# Sheet1.net
KiCad netlist of a schematic drawn in Altium Designer
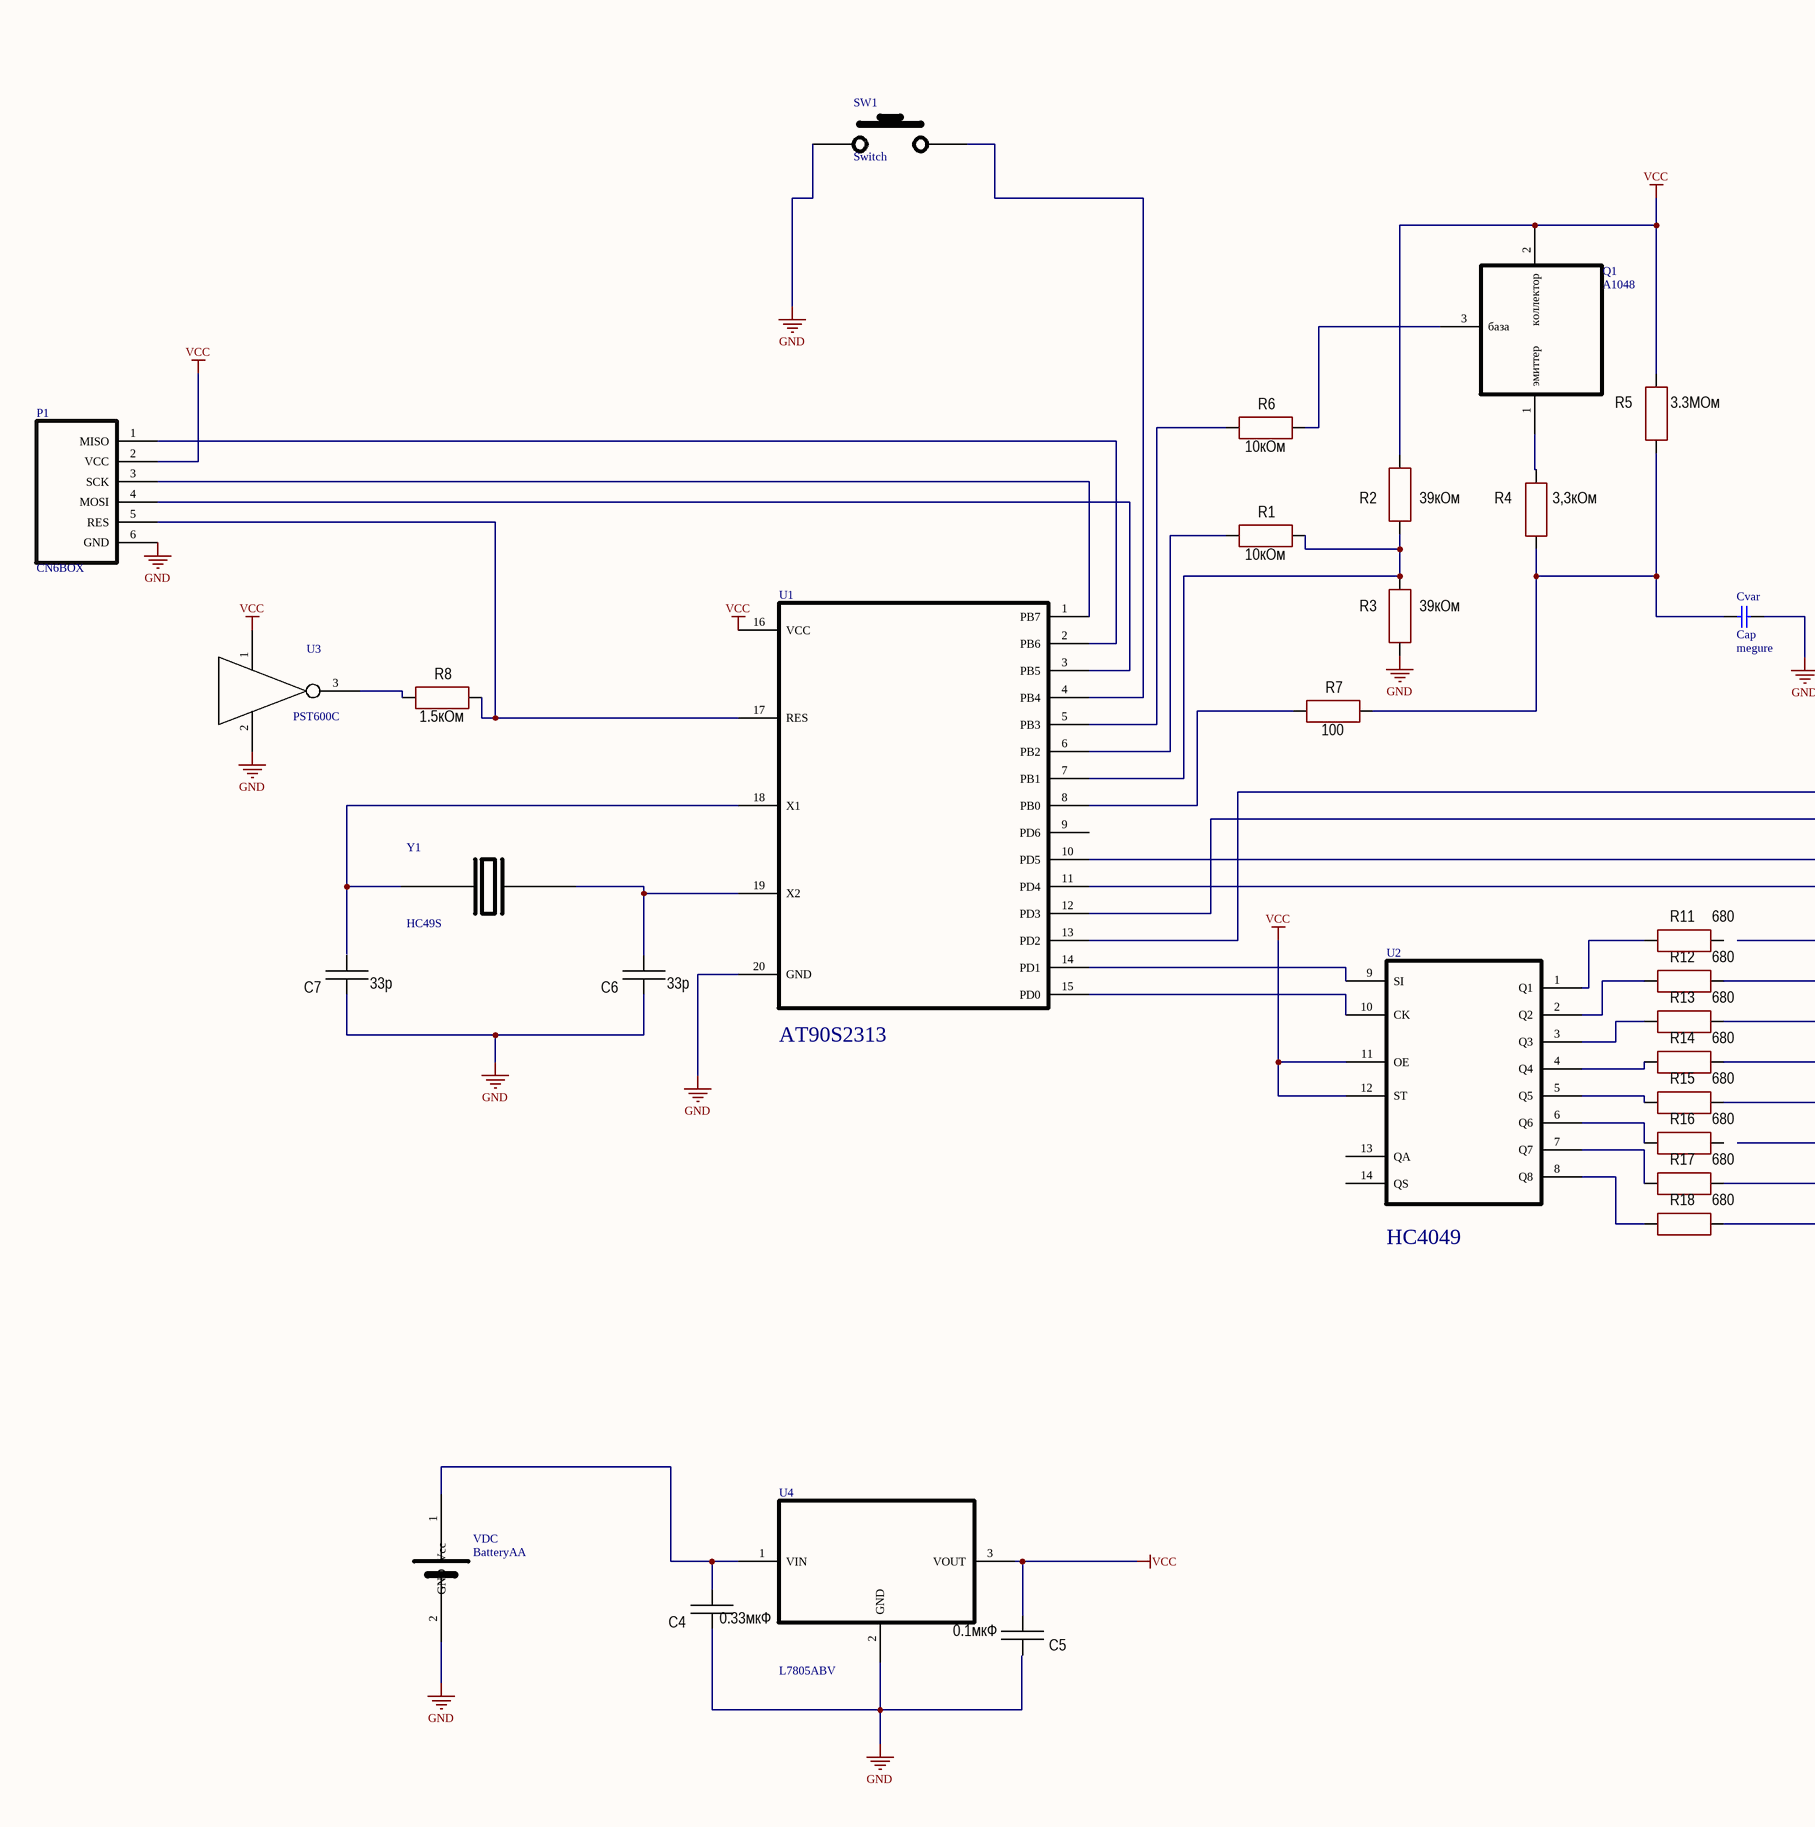
[diagram p0: Sheet1.SchDoc, left]
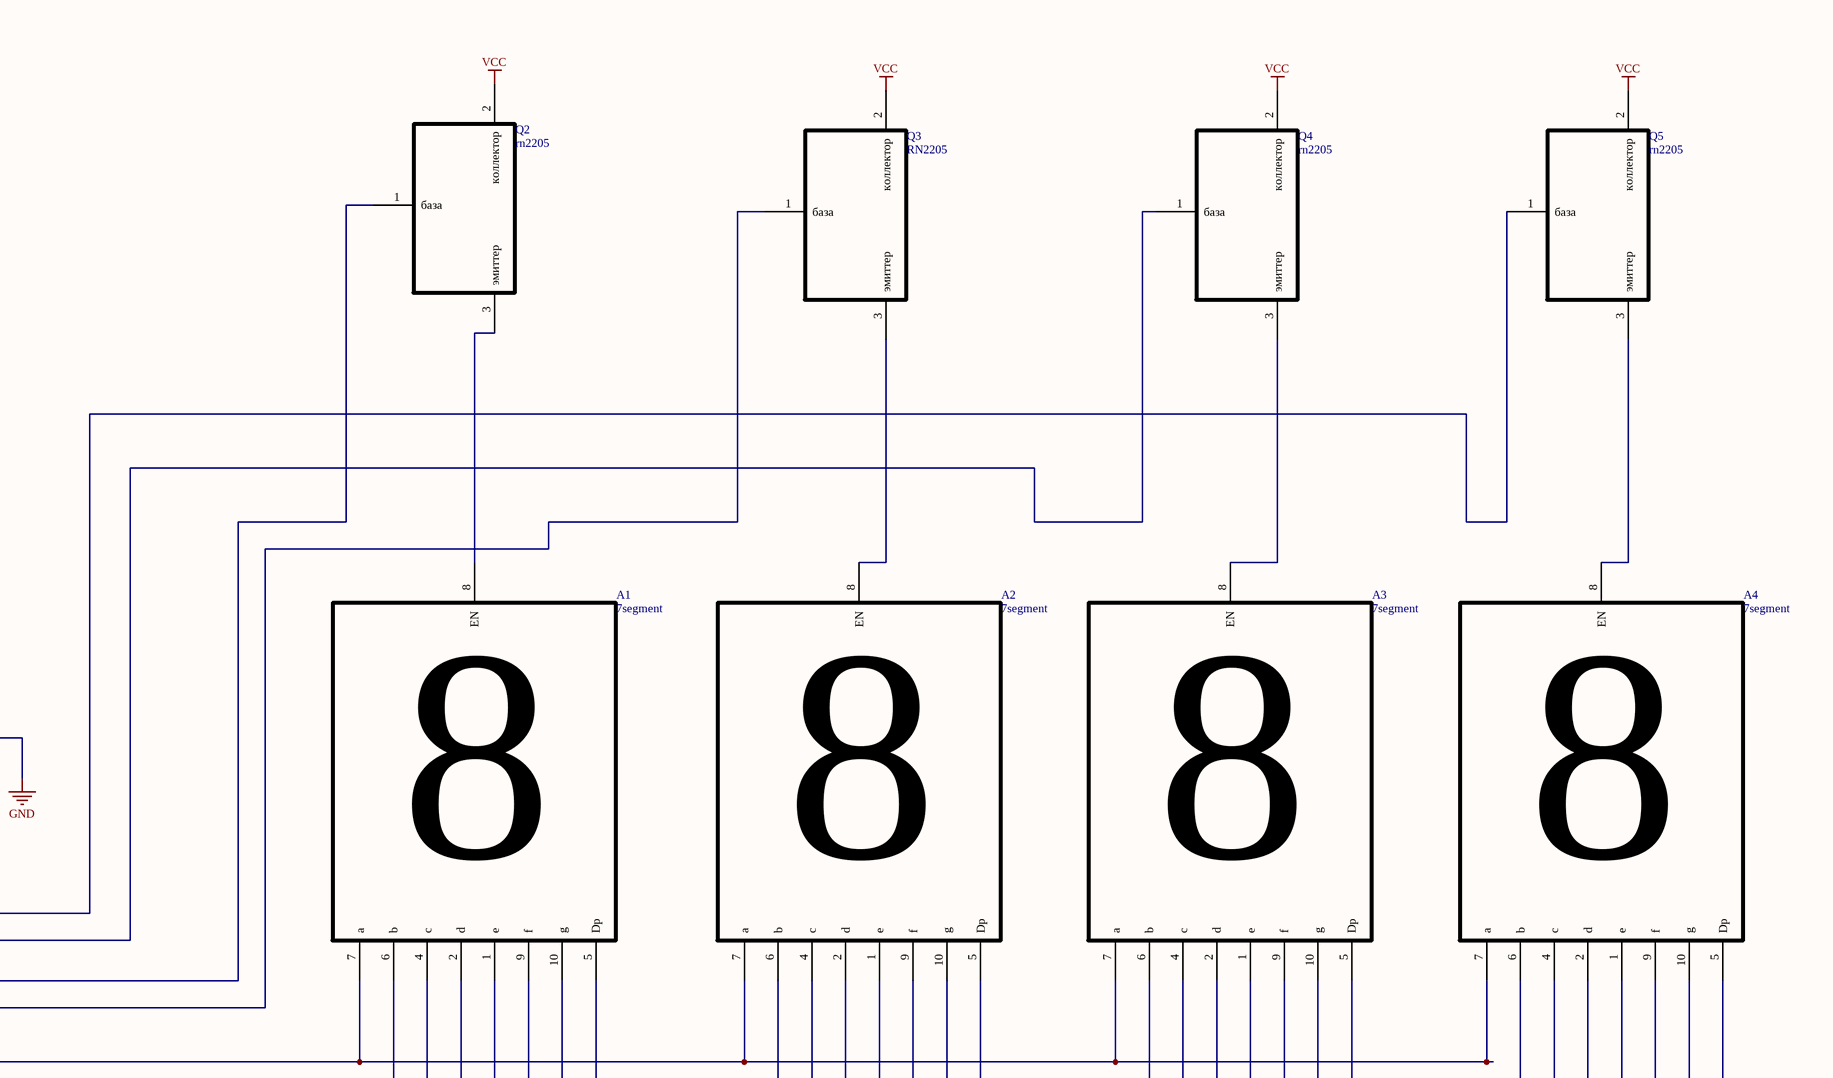
[diagram p1: Sheet1.SchDoc, right]

(export (version "E")
  (design (tool "Eeschema 10.0.6"))
  (components
    (comp (ref "A1") (value "7segment") (footprint "7segment") (libsource (lib "Schlib1") (part "7segment")))
    (comp (ref "A2") (value "7segment") (footprint "7segment") (libsource (lib "Schlib1") (part "7segment")))
    (comp (ref "A3") (value "7segment") (footprint "7segment") (libsource (lib "Schlib1") (part "7segment")))
    (comp (ref "A4") (value "7segment") (footprint "7segment") (libsource (lib "Schlib1") (part "7segment")))
    (comp (ref "C4") (value "0.33мкФ") (footprint "CH1206C") (libsource (lib "Discrete") (part "Capacitor")))
    (comp (ref "C5") (value "0.1мкФ") (footprint "CH0402C") (libsource (lib "Discrete") (part "Capacitor")))
    (comp (ref "C6") (value "33p") (footprint "CH0805C") (libsource (lib "Discrete") (part "Capacitor")))
    (comp (ref "C7") (value "33p") (footprint "CH0805C") (libsource (lib "Discrete") (part "Capacitor")))
    (comp (ref "Cvar")
      (value "Cap")
      (footprint "RAD-0.3")
      (description "Capacitor")
      (fields (field (name "ALTIUM_VALUE") "megure") (field (name "PUBLISHER") "Altium Limited"))
      (libsource (lib "Miscellaneous Devices") (part "Cap"))
    )
    (comp (ref "P1") (value "CN6BOX") (footprint "CN6BOX") (libsource (lib "Schlib1") (part "CN6BOX")))
    (comp (ref "Q1") (value "A1048") (footprint "PST600C") (libsource (lib "Schlib1") (part "A1048")))
    (comp (ref "Q2") (value "rn2205") (footprint "PST600C") (libsource (lib "Schlib1") (part "rn2205")))
    (comp (ref "Q3")
      (value "RN2205")
      (footprint "PST600C")
      (description "rn2205")
      (libsource (lib "Schlib1") (part "rn2205"))
    )
    (comp (ref "Q4") (value "rn2205") (footprint "PST600C") (libsource (lib "Schlib1") (part "rn2205")))
    (comp (ref "Q5") (value "rn2205") (footprint "PST600C") (libsource (lib "Schlib1") (part "rn2205")))
    (comp (ref "R1") (value "10кОм") (footprint "CH0402R") (libsource (lib "") (part "Resistor_1")))
    (comp (ref "R2") (value "39кОм") (footprint "CH0402R") (libsource (lib "Discrete") (part "Resistor")))
    (comp (ref "R3") (value "39кОм") (footprint "CH0402R") (libsource (lib "Discrete") (part "Resistor")))
    (comp (ref "R4") (value "3,3кОм") (footprint "CH0402R") (libsource (lib "Discrete") (part "Resistor")))
    (comp (ref "R5") (value "3.3МОм") (footprint "CH0402R") (libsource (lib "Discrete") (part "Resistor")))
    (comp (ref "R6") (value "10кОм") (footprint "CH0402R") (libsource (lib "") (part "Resistor_1")))
    (comp (ref "R7") (value "100") (footprint "CH0402R") (libsource (lib "") (part "Resistor_1")))
    (comp (ref "R8") (value "1.5кОм") (footprint "CH0402R") (libsource (lib "") (part "Resistor_1")))
    (comp (ref "R11") (value "680") (footprint "CH1206R") (libsource (lib "") (part "Resistor_1")))
    (comp (ref "R12") (value "680") (footprint "CH1206R") (libsource (lib "") (part "Resistor_1")))
    (comp (ref "R13") (value "680") (footprint "CH1206R") (libsource (lib "") (part "Resistor_1")))
    (comp (ref "R14") (value "680") (footprint "CH1206R") (libsource (lib "") (part "Resistor_1")))
    (comp (ref "R15") (value "680") (footprint "CH1206R") (libsource (lib "") (part "Resistor_1")))
    (comp (ref "R16") (value "680") (footprint "CH1206R") (libsource (lib "") (part "Resistor_1")))
    (comp (ref "R17") (value "680") (footprint "CH1206R") (libsource (lib "") (part "Resistor_1")))
    (comp (ref "R18") (value "680") (footprint "CH1206R") (libsource (lib "") (part "Resistor_1")))
    (comp (ref "SW1") (value "Switch") (footprint "SWITCH") (libsource (lib "Schlib1") (part "Switch")))
    (comp (ref "U1")
      (value "AT90S2313")
      (footprint "PcbLib1:AT90S2313")
      (libsource (lib "Schlib1") (part "AT90S2313"))
    )
    (comp (ref "U2") (value "HC4049") (footprint "HC4049") (libsource (lib "Schlib1") (part "HC4049")))
    (comp (ref "U3") (value "PST600C") (footprint "PST600C") (libsource (lib "Schlib1") (part "PST600C")))
    (comp (ref "U4")
      (value "L7805ABV")
      (footprint "7805")
      (description "7805")
      (libsource (lib "Schlib1") (part "7805"))
    )
    (comp (ref "VDC")
      (value "BatteryAA")
      (footprint "Battery")
      (libsource (lib "Schlib1") (part "BatteryAA"))
    )
    (comp (ref "Y1") (value "HC49S") (footprint "HC49S") (libsource (lib "Schlib1") (part "HC49S")))
  )
  (nets
    (net (code "1") (name "GND") (class "Default")
      (node (ref "C4") (pin "1") (pinfunction "1_1") (pintype "power_in"))
      (node (ref "C6") (pin "1") (pinfunction "1_1") (pintype "power_in"))
      (node (ref "C7") (pin "1") (pinfunction "1_1") (pintype "power_in"))
      (node (ref "Cvar") (pin "2") (pinfunction "2_2") (pintype "passive"))
      (node (ref "P1") (pin "6") (pinfunction "GND_6") (pintype "passive"))
      (node (ref "R3") (pin "1") (pinfunction "1_1") (pintype "passive"))
      (node (ref "SW1") (pin "1") (pinfunction "1_1") (pintype "passive"))
      (node (ref "U1") (pin "20") (pinfunction "GND_20") (pintype "passive"))
      (node (ref "U3") (pin "2") (pinfunction "QS_2") (pintype "passive"))
      (node (ref "U4") (pin "2") (pinfunction "GND_2") (pintype "passive"))
      (node (ref "VDC") (pin "2") (pinfunction "GND_2") (pintype "passive"))
    )
    (net (code "2") (name "Net-(A1-Dp)") (class "Default")
      (node (ref "A1") (pin "5") (pinfunction "Dp_5") (pintype "passive"))
      (node (ref "A2") (pin "5") (pinfunction "Dp_5") (pintype "passive"))
      (node (ref "A3") (pin "5") (pinfunction "Dp_5") (pintype "passive"))
      (node (ref "A4") (pin "5") (pinfunction "Dp_5") (pintype "passive"))
      (node (ref "R18") (pin "2") (pinfunction "2_2") (pintype "passive"))
    )
    (net (code "3") (name "Net-(A1-EN)") (class "Default")
      (node (ref "A1") (pin "8") (pinfunction "EN_8") (pintype "passive"))
      (node (ref "Q2") (pin "3") (pinfunction "эмиттер_3") (pintype "passive"))
    )
    (net (code "4") (name "Net-(A1-a)") (class "Default")
      (node (ref "A1") (pin "7") (pinfunction "a_7") (pintype "passive"))
      (node (ref "A2") (pin "7") (pinfunction "a_7") (pintype "passive"))
      (node (ref "A3") (pin "7") (pinfunction "a_7") (pintype "passive"))
      (node (ref "A4") (pin "7") (pinfunction "a_7") (pintype "passive"))
    )
    (net (code "5") (name "Net-(A1-b)") (class "Default")
      (node (ref "A1") (pin "6") (pinfunction "b_6") (pintype "passive"))
      (node (ref "A2") (pin "6") (pinfunction "b_6") (pintype "passive"))
      (node (ref "A3") (pin "6") (pinfunction "b_6") (pintype "passive"))
      (node (ref "A4") (pin "6") (pinfunction "b_6") (pintype "passive"))
      (node (ref "R12") (pin "2") (pinfunction "2_2") (pintype "passive"))
    )
    (net (code "6") (name "Net-(A1-c)") (class "Default")
      (node (ref "A1") (pin "4") (pinfunction "c_4") (pintype "passive"))
      (node (ref "A2") (pin "4") (pinfunction "c_4") (pintype "passive"))
      (node (ref "A3") (pin "4") (pinfunction "c_4") (pintype "passive"))
      (node (ref "A4") (pin "4") (pinfunction "c_4") (pintype "passive"))
      (node (ref "R13") (pin "2") (pinfunction "2_2") (pintype "passive"))
    )
    (net (code "7") (name "Net-(A1-d)") (class "Default")
      (node (ref "A1") (pin "2") (pinfunction "d_2") (pintype "passive"))
      (node (ref "A2") (pin "2") (pinfunction "d_2") (pintype "passive"))
      (node (ref "A3") (pin "2") (pinfunction "d_2") (pintype "passive"))
      (node (ref "A4") (pin "2") (pinfunction "d_2") (pintype "passive"))
      (node (ref "R14") (pin "2") (pinfunction "2_2") (pintype "passive"))
    )
    (net (code "8") (name "Net-(A1-e)") (class "Default")
      (node (ref "A1") (pin "1") (pinfunction "e_1") (pintype "passive"))
      (node (ref "A2") (pin "1") (pinfunction "e_1") (pintype "passive"))
      (node (ref "A3") (pin "1") (pinfunction "e_1") (pintype "passive"))
      (node (ref "A4") (pin "1") (pinfunction "e_1") (pintype "passive"))
      (node (ref "R15") (pin "2") (pinfunction "2_2") (pintype "passive"))
    )
    (net (code "9") (name "Net-(A1-f)") (class "Default")
      (node (ref "A1") (pin "9") (pinfunction "f_9") (pintype "passive"))
      (node (ref "A2") (pin "9") (pinfunction "f_9") (pintype "passive"))
      (node (ref "A3") (pin "9") (pinfunction "f_9") (pintype "passive"))
      (node (ref "A4") (pin "9") (pinfunction "f_9") (pintype "passive"))
    )
    (net (code "10") (name "Net-(A1-g)") (class "Default")
      (node (ref "A1") (pin "10") (pinfunction "g_10") (pintype "passive"))
      (node (ref "A2") (pin "10") (pinfunction "g_10") (pintype "passive"))
      (node (ref "A3") (pin "10") (pinfunction "g_10") (pintype "passive"))
      (node (ref "A4") (pin "10") (pinfunction "g_10") (pintype "passive"))
      (node (ref "R17") (pin "2") (pinfunction "2_2") (pintype "passive"))
    )
    (net (code "11") (name "Net-(A2-EN)") (class "Default")
      (node (ref "A2") (pin "8") (pinfunction "EN_8") (pintype "passive"))
      (node (ref "Q3") (pin "3") (pinfunction "эмиттер_3") (pintype "passive"))
    )
    (net (code "12") (name "Net-(A3-EN)") (class "Default")
      (node (ref "A3") (pin "8") (pinfunction "EN_8") (pintype "passive"))
      (node (ref "Q4") (pin "3") (pinfunction "эмиттер_3") (pintype "passive"))
    )
    (net (code "13") (name "Net-(A4-EN)") (class "Default")
      (node (ref "A4") (pin "8") (pinfunction "EN_8") (pintype "passive"))
      (node (ref "Q5") (pin "3") (pinfunction "эмиттер_3") (pintype "passive"))
    )
    (net (code "14") (name "Net-(Cvar-Pad1)") (class "Default")
      (node (ref "Cvar") (pin "1") (pinfunction "1_1") (pintype "passive"))
      (node (ref "R4") (pin "1") (pinfunction "1_1") (pintype "passive"))
      (node (ref "R5") (pin "1") (pinfunction "1_1") (pintype "passive"))
      (node (ref "R7") (pin "2") (pinfunction "2_2") (pintype "passive"))
    )
    (net (code "15") (name "Net-(P1-MISO)") (class "Default")
      (node (ref "P1") (pin "1") (pinfunction "MISO_1") (pintype "passive"))
      (node (ref "U1") (pin "2") (pinfunction "PB6_2") (pintype "passive"))
    )
    (net (code "16") (name "Net-(P1-MOSI)") (class "Default")
      (node (ref "P1") (pin "4") (pinfunction "MOSI_4") (pintype "passive"))
      (node (ref "U1") (pin "3") (pinfunction "PB5_3") (pintype "passive"))
    )
    (net (code "17") (name "Net-(P1-RES)") (class "Default")
      (node (ref "P1") (pin "5") (pinfunction "RES_5") (pintype "passive"))
      (node (ref "R8") (pin "2") (pinfunction "2_2") (pintype "passive"))
      (node (ref "U1") (pin "17") (pinfunction "RES_17") (pintype "passive"))
    )
    (net (code "18") (name "Net-(P1-SCK)") (class "Default")
      (node (ref "P1") (pin "3") (pinfunction "SCK_3") (pintype "passive"))
      (node (ref "U1") (pin "1") (pinfunction "PB7_1") (pintype "passive"))
    )
    (net (code "19") (name "Net-(Q1-база)") (class "Default")
      (node (ref "Q1") (pin "3") (pinfunction "база_3") (pintype "passive"))
      (node (ref "R6") (pin "2") (pinfunction "2_2") (pintype "passive"))
    )
    (net (code "20") (name "Net-(Q1-эмиттер)") (class "Default")
      (node (ref "Q1") (pin "1") (pinfunction "эмиттер_1") (pintype "passive"))
      (node (ref "R4") (pin "2") (pinfunction "2_2") (pintype "passive"))
    )
    (net (code "21") (name "Net-(Q2-база)") (class "Default")
      (node (ref "Q2") (pin "1") (pinfunction "база_1") (pintype "passive"))
      (node (ref "U1") (pin "10") (pinfunction "PD5_10") (pintype "passive"))
    )
    (net (code "22") (name "Net-(Q3-база)") (class "Default")
      (node (ref "Q3") (pin "1") (pinfunction "база_1") (pintype "passive"))
      (node (ref "U1") (pin "11") (pinfunction "PD4_11") (pintype "passive"))
    )
    (net (code "23") (name "Net-(Q4-база)") (class "Default")
      (node (ref "Q4") (pin "1") (pinfunction "база_1") (pintype "passive"))
      (node (ref "U1") (pin "12") (pinfunction "PD3_12") (pintype "passive"))
    )
    (net (code "24") (name "Net-(Q5-база)") (class "Default")
      (node (ref "Q5") (pin "1") (pinfunction "база_1") (pintype "passive"))
      (node (ref "U1") (pin "13") (pinfunction "PD2_13") (pintype "passive"))
    )
    (net (code "25") (name "Net-(R8-Pad1)") (class "Default")
      (node (ref "R8") (pin "1") (pinfunction "1_1") (pintype "passive"))
      (node (ref "U3") (pin "3") (pinfunction "QS_3") (pintype "passive"))
    )
    (net (code "26") (name "Net-(U1-PB0)") (class "Default")
      (node (ref "R7") (pin "1") (pinfunction "1_1") (pintype "passive"))
      (node (ref "U1") (pin "8") (pinfunction "PB0_8") (pintype "passive"))
    )
    (net (code "27") (name "Net-(U1-PB1)") (class "Default")
      (node (ref "R1") (pin "2") (pinfunction "2_2") (pintype "passive"))
      (node (ref "R2") (pin "1") (pinfunction "1_1") (pintype "passive"))
      (node (ref "R3") (pin "2") (pinfunction "2_2") (pintype "passive"))
      (node (ref "U1") (pin "7") (pinfunction "PB1_7") (pintype "passive"))
    )
    (net (code "28") (name "Net-(U1-PB2)") (class "Default")
      (node (ref "R1") (pin "1") (pinfunction "1_1") (pintype "passive"))
      (node (ref "U1") (pin "6") (pinfunction "PB2_6") (pintype "passive"))
    )
    (net (code "29") (name "Net-(U1-PB3)") (class "Default")
      (node (ref "R6") (pin "1") (pinfunction "1_1") (pintype "passive"))
      (node (ref "U1") (pin "5") (pinfunction "PB3_5") (pintype "passive"))
    )
    (net (code "30") (name "Net-(U1-PB4)") (class "Default")
      (node (ref "SW1") (pin "2") (pinfunction "2_2") (pintype "passive"))
      (node (ref "U1") (pin "4") (pinfunction "PB4_4") (pintype "passive"))
    )
    (net (code "31") (name "Net-(U1-PD0)") (class "Default")
      (node (ref "U1") (pin "15") (pinfunction "PD0_15") (pintype "passive"))
      (node (ref "U2") (pin "10") (pinfunction "CK_10") (pintype "passive"))
    )
    (net (code "32") (name "Net-(U1-PD1)") (class "Default")
      (node (ref "U1") (pin "14") (pinfunction "PD1_14") (pintype "passive"))
      (node (ref "U2") (pin "9") (pinfunction "SI_9") (pintype "passive"))
    )
    (net (code "33") (name "Net-(U1-X1)") (class "Default")
      (node (ref "U1") (pin "18") (pinfunction "X1_18") (pintype "passive"))
      (node (ref "Y1") (pin "1") (pinfunction "QS_1") (pintype "passive"))
    )
    (net (code "34") (name "Net-(U1-X2)") (class "Default")
      (node (ref "C6") (pin "2") (pinfunction "2_2") (pintype "power_in"))
      (node (ref "U1") (pin "19") (pinfunction "X2_19") (pintype "passive"))
      (node (ref "Y1") (pin "2") (pinfunction "QS_2") (pintype "passive"))
    )
    (net (code "35") (name "Net-(U2-Q1)") (class "Default")
      (node (ref "R11") (pin "1") (pinfunction "1_1") (pintype "passive"))
      (node (ref "U2") (pin "1") (pinfunction "Q1_1") (pintype "passive"))
    )
    (net (code "36") (name "Net-(U2-Q2)") (class "Default")
      (node (ref "R12") (pin "1") (pinfunction "1_1") (pintype "passive"))
      (node (ref "U2") (pin "2") (pinfunction "Q2_2") (pintype "passive"))
    )
    (net (code "37") (name "Net-(U2-Q3)") (class "Default")
      (node (ref "R13") (pin "1") (pinfunction "1_1") (pintype "passive"))
      (node (ref "U2") (pin "3") (pinfunction "Q3_3") (pintype "passive"))
    )
    (net (code "38") (name "Net-(U2-Q4)") (class "Default")
      (node (ref "R14") (pin "1") (pinfunction "1_1") (pintype "passive"))
      (node (ref "U2") (pin "4") (pinfunction "Q4_4") (pintype "passive"))
    )
    (net (code "39") (name "Net-(U2-Q5)") (class "Default")
      (node (ref "R15") (pin "1") (pinfunction "1_1") (pintype "passive"))
      (node (ref "U2") (pin "5") (pinfunction "Q5_5") (pintype "passive"))
    )
    (net (code "40") (name "Net-(U2-Q6)") (class "Default")
      (node (ref "R16") (pin "1") (pinfunction "1_1") (pintype "passive"))
      (node (ref "U2") (pin "6") (pinfunction "Q6_6") (pintype "passive"))
    )
    (net (code "41") (name "Net-(U2-Q7)") (class "Default")
      (node (ref "R17") (pin "1") (pinfunction "1_1") (pintype "passive"))
      (node (ref "U2") (pin "7") (pinfunction "Q7_7") (pintype "passive"))
    )
    (net (code "42") (name "Net-(U2-Q8)") (class "Default")
      (node (ref "R18") (pin "1") (pinfunction "1_1") (pintype "passive"))
      (node (ref "U2") (pin "8") (pinfunction "Q8_8") (pintype "passive"))
    )
    (net (code "43") (name "Net-(U4-VIN)") (class "Default")
      (node (ref "C4") (pin "2") (pinfunction "2_2") (pintype "power_in"))
      (node (ref "U4") (pin "1") (pinfunction "VIN_1") (pintype "passive"))
      (node (ref "VDC") (pin "1") (pinfunction "Vcc_1") (pintype "passive"))
    )
    (net (code "44") (name "VCC") (class "Default")
      (node (ref "C5") (pin "1") (pinfunction "1_1") (pintype "power_in"))
      (node (ref "P1") (pin "2") (pinfunction "VCC_2") (pintype "passive"))
      (node (ref "Q1") (pin "2") (pinfunction "коллектор_2") (pintype "passive"))
      (node (ref "Q2") (pin "2") (pinfunction "коллектор_2") (pintype "passive"))
      (node (ref "Q3") (pin "2") (pinfunction "коллектор_2") (pintype "passive"))
      (node (ref "Q4") (pin "2") (pinfunction "коллектор_2") (pintype "passive"))
      (node (ref "Q5") (pin "2") (pinfunction "коллектор_2") (pintype "passive"))
      (node (ref "R2") (pin "2") (pinfunction "2_2") (pintype "passive"))
      (node (ref "R5") (pin "2") (pinfunction "2_2") (pintype "passive"))
      (node (ref "U1") (pin "16") (pinfunction "VCC_16") (pintype "passive"))
      (node (ref "U2") (pin "11") (pinfunction "OE_11") (pintype "passive"))
      (node (ref "U2") (pin "12") (pinfunction "ST_12") (pintype "passive"))
      (node (ref "U3") (pin "1") (pinfunction "QS_1") (pintype "passive"))
      (node (ref "U4") (pin "3") (pinfunction "VOUT_3") (pintype "passive"))
    )
    (net (code "45") (name "unconnected-(C5-Pad2)") (class "Default")
      (node (ref "C5") (pin "2") (pinfunction "2_2") (pintype "power_in"))
    )
    (net (code "46") (name "unconnected-(C7-Pad2)") (class "Default")
      (node (ref "C7") (pin "2") (pinfunction "2_2") (pintype "power_in"))
    )
    (net (code "47") (name "unconnected-(R11-Pad2)") (class "Default")
      (node (ref "R11") (pin "2") (pinfunction "2_2") (pintype "passive"))
    )
    (net (code "48") (name "unconnected-(R16-Pad2)") (class "Default")
      (node (ref "R16") (pin "2") (pinfunction "2_2") (pintype "passive"))
    )
    (net (code "49") (name "unconnected-(U1-PD6-Pad9)") (class "Default")
      (node (ref "U1") (pin "9") (pinfunction "PD6_9") (pintype "passive"))
    )
    (net (code "50") (name "unconnected-(U2-QA-Pad13)") (class "Default")
      (node (ref "U2") (pin "13") (pinfunction "QA_13") (pintype "passive"))
    )
    (net (code "51") (name "unconnected-(U2-QS-Pad14)") (class "Default")
      (node (ref "U2") (pin "14") (pinfunction "QS_14") (pintype "passive"))
    )
  )
)
